# opto4.net
KiCad netlist of a schematic drawn in EAGLE
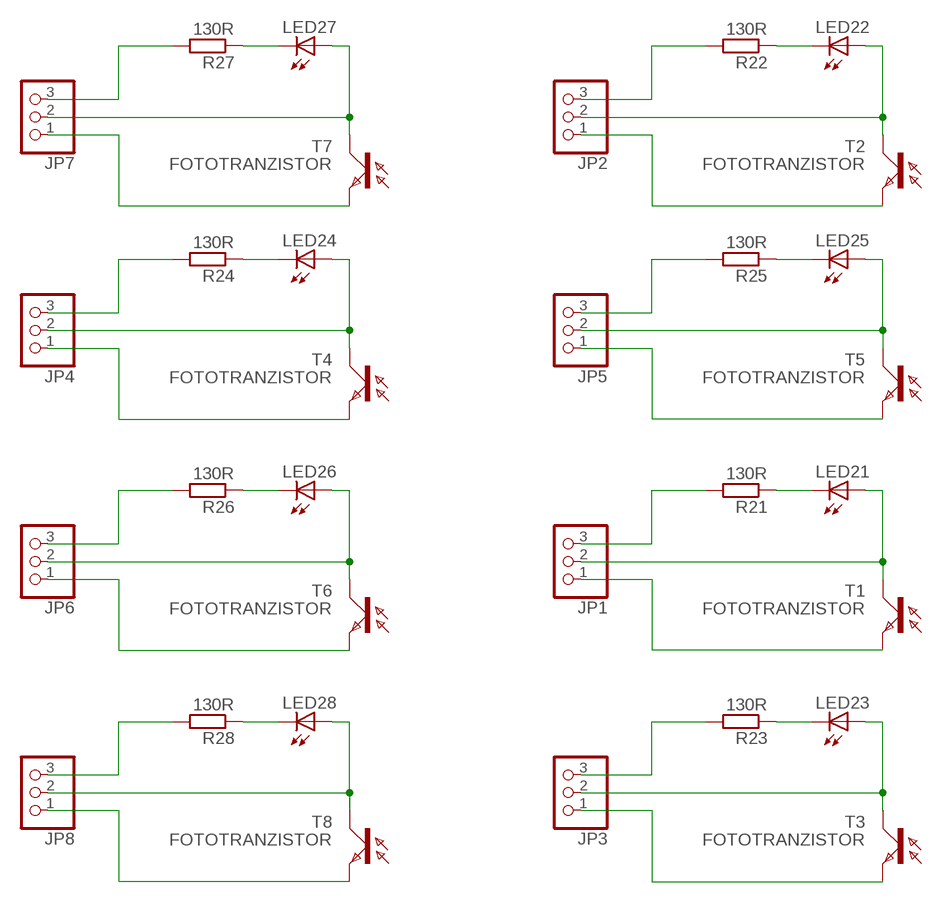
[diagram p0: schematic, sheet 1]

(export (version "E")
  (design (tool "Eeschema 10.0.6"))
  (components
    (comp (ref "JP1")
      (value "PINHD-1X3/90")
      (footprint "eagle-import:1X03_90")
      (libsource (lib "eagle-import") (part "PINHD-1X3/90"))
    )
    (comp (ref "JP2")
      (value "PINHD-1X3/90")
      (footprint "eagle-import:1X03_90")
      (libsource (lib "eagle-import") (part "PINHD-1X3/90"))
    )
    (comp (ref "JP3")
      (value "PINHD-1X3/90")
      (footprint "eagle-import:1X03_90")
      (libsource (lib "eagle-import") (part "PINHD-1X3/90"))
    )
    (comp (ref "JP4")
      (value "PINHD-1X3/90")
      (footprint "eagle-import:1X03_90")
      (libsource (lib "eagle-import") (part "PINHD-1X3/90"))
    )
    (comp (ref "JP5")
      (value "PINHD-1X3/90")
      (footprint "eagle-import:1X03_90")
      (libsource (lib "eagle-import") (part "PINHD-1X3/90"))
    )
    (comp (ref "JP6")
      (value "PINHD-1X3/90")
      (footprint "eagle-import:1X03_90")
      (libsource (lib "eagle-import") (part "PINHD-1X3/90"))
    )
    (comp (ref "JP7")
      (value "PINHD-1X3/90")
      (footprint "eagle-import:1X03_90")
      (libsource (lib "eagle-import") (part "PINHD-1X3/90"))
    )
    (comp (ref "JP8")
      (value "PINHD-1X3/90")
      (footprint "eagle-import:1X03_90")
      (libsource (lib "eagle-import") (part "PINHD-1X3/90"))
    )
    (comp (ref "LED21")
      (value "LED3MM")
      (footprint "eagle-import:LED3MM")
      (libsource (lib "eagle-import") (part "LED3MM"))
    )
    (comp (ref "LED22")
      (value "LED3MM")
      (footprint "eagle-import:LED3MM")
      (libsource (lib "eagle-import") (part "LED3MM"))
    )
    (comp (ref "LED23")
      (value "LED3MM")
      (footprint "eagle-import:LED3MM")
      (libsource (lib "eagle-import") (part "LED3MM"))
    )
    (comp (ref "LED24")
      (value "LED3MM")
      (footprint "eagle-import:LED3MM")
      (libsource (lib "eagle-import") (part "LED3MM"))
    )
    (comp (ref "LED25")
      (value "LED3MM")
      (footprint "eagle-import:LED3MM")
      (libsource (lib "eagle-import") (part "LED3MM"))
    )
    (comp (ref "LED26")
      (value "LED3MM")
      (footprint "eagle-import:LED3MM")
      (libsource (lib "eagle-import") (part "LED3MM"))
    )
    (comp (ref "LED27")
      (value "LED3MM")
      (footprint "eagle-import:LED3MM")
      (libsource (lib "eagle-import") (part "LED3MM"))
    )
    (comp (ref "LED28")
      (value "LED3MM")
      (footprint "eagle-import:LED3MM")
      (libsource (lib "eagle-import") (part "LED3MM"))
    )
    (comp (ref "R21")
      (value "130R")
      (footprint "eagle-import:R1206")
      (libsource (lib "eagle-import") (part "R-EU_R1206"))
    )
    (comp (ref "R22")
      (value "130R")
      (footprint "eagle-import:R1206")
      (libsource (lib "eagle-import") (part "R-EU_R1206"))
    )
    (comp (ref "R23")
      (value "130R")
      (footprint "eagle-import:R1206")
      (libsource (lib "eagle-import") (part "R-EU_R1206"))
    )
    (comp (ref "R24")
      (value "130R")
      (footprint "eagle-import:R1206")
      (libsource (lib "eagle-import") (part "R-EU_R1206"))
    )
    (comp (ref "R25")
      (value "130R")
      (footprint "eagle-import:R1206")
      (libsource (lib "eagle-import") (part "R-EU_R1206"))
    )
    (comp (ref "R26")
      (value "130R")
      (footprint "eagle-import:R1206")
      (libsource (lib "eagle-import") (part "R-EU_R1206"))
    )
    (comp (ref "R27")
      (value "130R")
      (footprint "eagle-import:R1206")
      (libsource (lib "eagle-import") (part "R-EU_R1206"))
    )
    (comp (ref "R28")
      (value "130R")
      (footprint "eagle-import:R1206")
      (libsource (lib "eagle-import") (part "R-EU_R1206"))
    )
    (comp (ref "T1")
      (value "FOTOTRANZISTOR")
      (footprint "eagle-import:BPX81")
      (libsource (lib "eagle-import") (part "FOTOTRANZISTOR"))
    )
    (comp (ref "T2")
      (value "FOTOTRANZISTOR")
      (footprint "eagle-import:BPX81")
      (libsource (lib "eagle-import") (part "FOTOTRANZISTOR"))
    )
    (comp (ref "T3")
      (value "FOTOTRANZISTOR")
      (footprint "eagle-import:BPX81")
      (libsource (lib "eagle-import") (part "FOTOTRANZISTOR"))
    )
    (comp (ref "T4")
      (value "FOTOTRANZISTOR")
      (footprint "eagle-import:BPX81")
      (libsource (lib "eagle-import") (part "FOTOTRANZISTOR"))
    )
    (comp (ref "T5")
      (value "FOTOTRANZISTOR")
      (footprint "eagle-import:BPX81")
      (libsource (lib "eagle-import") (part "FOTOTRANZISTOR"))
    )
    (comp (ref "T6")
      (value "FOTOTRANZISTOR")
      (footprint "eagle-import:BPX81")
      (libsource (lib "eagle-import") (part "FOTOTRANZISTOR"))
    )
    (comp (ref "T7")
      (value "FOTOTRANZISTOR")
      (footprint "eagle-import:BPX81")
      (libsource (lib "eagle-import") (part "FOTOTRANZISTOR"))
    )
    (comp (ref "T8")
      (value "FOTOTRANZISTOR")
      (footprint "eagle-import:BPX81")
      (libsource (lib "eagle-import") (part "FOTOTRANZISTOR"))
    )
  )
  (nets
    (net (code "1") (name "Net-(JP1-Pad1)") (class "Default")
      (node (ref "JP1") (pin "1") (pinfunction "1_1") (pintype "passive"))
      (node (ref "T1") (pin "E") (pinfunction "E_E") (pintype "passive"))
    )
    (net (code "2") (name "Net-(JP1-Pad2)") (class "Default")
      (node (ref "JP1") (pin "2") (pinfunction "2_2") (pintype "passive"))
      (node (ref "LED21") (pin "A") (pinfunction "A_A") (pintype "passive"))
      (node (ref "T1") (pin "C") (pinfunction "C_C") (pintype "passive"))
    )
    (net (code "3") (name "Net-(JP1-Pad3)") (class "Default")
      (node (ref "JP1") (pin "3") (pinfunction "3_3") (pintype "passive"))
      (node (ref "R21") (pin "2") (pinfunction "2_2") (pintype "passive"))
    )
    (net (code "4") (name "Net-(JP2-Pad1)") (class "Default")
      (node (ref "JP2") (pin "1") (pinfunction "1_1") (pintype "passive"))
      (node (ref "T2") (pin "E") (pinfunction "E_E") (pintype "passive"))
    )
    (net (code "5") (name "Net-(JP2-Pad2)") (class "Default")
      (node (ref "JP2") (pin "2") (pinfunction "2_2") (pintype "passive"))
      (node (ref "LED22") (pin "A") (pinfunction "A_A") (pintype "passive"))
      (node (ref "T2") (pin "C") (pinfunction "C_C") (pintype "passive"))
    )
    (net (code "6") (name "Net-(JP2-Pad3)") (class "Default")
      (node (ref "JP2") (pin "3") (pinfunction "3_3") (pintype "passive"))
      (node (ref "R22") (pin "2") (pinfunction "2_2") (pintype "passive"))
    )
    (net (code "7") (name "Net-(JP3-Pad1)") (class "Default")
      (node (ref "JP3") (pin "1") (pinfunction "1_1") (pintype "passive"))
      (node (ref "T3") (pin "E") (pinfunction "E_E") (pintype "passive"))
    )
    (net (code "8") (name "Net-(JP3-Pad2)") (class "Default")
      (node (ref "JP3") (pin "2") (pinfunction "2_2") (pintype "passive"))
      (node (ref "LED23") (pin "A") (pinfunction "A_A") (pintype "passive"))
      (node (ref "T3") (pin "C") (pinfunction "C_C") (pintype "passive"))
    )
    (net (code "9") (name "Net-(JP3-Pad3)") (class "Default")
      (node (ref "JP3") (pin "3") (pinfunction "3_3") (pintype "passive"))
      (node (ref "R23") (pin "2") (pinfunction "2_2") (pintype "passive"))
    )
    (net (code "10") (name "Net-(JP4-Pad1)") (class "Default")
      (node (ref "JP4") (pin "1") (pinfunction "1_1") (pintype "passive"))
      (node (ref "T4") (pin "E") (pinfunction "E_E") (pintype "passive"))
    )
    (net (code "11") (name "Net-(JP4-Pad2)") (class "Default")
      (node (ref "JP4") (pin "2") (pinfunction "2_2") (pintype "passive"))
      (node (ref "LED24") (pin "A") (pinfunction "A_A") (pintype "passive"))
      (node (ref "T4") (pin "C") (pinfunction "C_C") (pintype "passive"))
    )
    (net (code "12") (name "Net-(JP4-Pad3)") (class "Default")
      (node (ref "JP4") (pin "3") (pinfunction "3_3") (pintype "passive"))
      (node (ref "R24") (pin "2") (pinfunction "2_2") (pintype "passive"))
    )
    (net (code "13") (name "Net-(JP5-Pad1)") (class "Default")
      (node (ref "JP5") (pin "1") (pinfunction "1_1") (pintype "passive"))
      (node (ref "T5") (pin "E") (pinfunction "E_E") (pintype "passive"))
    )
    (net (code "14") (name "Net-(JP5-Pad2)") (class "Default")
      (node (ref "JP5") (pin "2") (pinfunction "2_2") (pintype "passive"))
      (node (ref "LED25") (pin "A") (pinfunction "A_A") (pintype "passive"))
      (node (ref "T5") (pin "C") (pinfunction "C_C") (pintype "passive"))
    )
    (net (code "15") (name "Net-(JP5-Pad3)") (class "Default")
      (node (ref "JP5") (pin "3") (pinfunction "3_3") (pintype "passive"))
      (node (ref "R25") (pin "2") (pinfunction "2_2") (pintype "passive"))
    )
    (net (code "16") (name "Net-(JP6-Pad1)") (class "Default")
      (node (ref "JP6") (pin "1") (pinfunction "1_1") (pintype "passive"))
      (node (ref "T6") (pin "E") (pinfunction "E_E") (pintype "passive"))
    )
    (net (code "17") (name "Net-(JP6-Pad2)") (class "Default")
      (node (ref "JP6") (pin "2") (pinfunction "2_2") (pintype "passive"))
      (node (ref "LED26") (pin "A") (pinfunction "A_A") (pintype "passive"))
      (node (ref "T6") (pin "C") (pinfunction "C_C") (pintype "passive"))
    )
    (net (code "18") (name "Net-(JP6-Pad3)") (class "Default")
      (node (ref "JP6") (pin "3") (pinfunction "3_3") (pintype "passive"))
      (node (ref "R26") (pin "2") (pinfunction "2_2") (pintype "passive"))
    )
    (net (code "19") (name "Net-(JP7-Pad1)") (class "Default")
      (node (ref "JP7") (pin "1") (pinfunction "1_1") (pintype "passive"))
      (node (ref "T7") (pin "E") (pinfunction "E_E") (pintype "passive"))
    )
    (net (code "20") (name "Net-(JP7-Pad2)") (class "Default")
      (node (ref "JP7") (pin "2") (pinfunction "2_2") (pintype "passive"))
      (node (ref "LED27") (pin "A") (pinfunction "A_A") (pintype "passive"))
      (node (ref "T7") (pin "C") (pinfunction "C_C") (pintype "passive"))
    )
    (net (code "21") (name "Net-(JP7-Pad3)") (class "Default")
      (node (ref "JP7") (pin "3") (pinfunction "3_3") (pintype "passive"))
      (node (ref "R27") (pin "2") (pinfunction "2_2") (pintype "passive"))
    )
    (net (code "22") (name "Net-(JP8-Pad1)") (class "Default")
      (node (ref "JP8") (pin "1") (pinfunction "1_1") (pintype "passive"))
      (node (ref "T8") (pin "E") (pinfunction "E_E") (pintype "passive"))
    )
    (net (code "23") (name "Net-(JP8-Pad2)") (class "Default")
      (node (ref "JP8") (pin "2") (pinfunction "2_2") (pintype "passive"))
      (node (ref "LED28") (pin "A") (pinfunction "A_A") (pintype "passive"))
      (node (ref "T8") (pin "C") (pinfunction "C_C") (pintype "passive"))
    )
    (net (code "24") (name "Net-(JP8-Pad3)") (class "Default")
      (node (ref "JP8") (pin "3") (pinfunction "3_3") (pintype "passive"))
      (node (ref "R28") (pin "2") (pinfunction "2_2") (pintype "passive"))
    )
    (net (code "25") (name "Net-(LED21-C)") (class "Default")
      (node (ref "LED21") (pin "K") (pinfunction "C_K") (pintype "passive"))
      (node (ref "R21") (pin "1") (pinfunction "1_1") (pintype "passive"))
    )
    (net (code "26") (name "Net-(LED22-C)") (class "Default")
      (node (ref "LED22") (pin "K") (pinfunction "C_K") (pintype "passive"))
      (node (ref "R22") (pin "1") (pinfunction "1_1") (pintype "passive"))
    )
    (net (code "27") (name "Net-(LED23-C)") (class "Default")
      (node (ref "LED23") (pin "K") (pinfunction "C_K") (pintype "passive"))
      (node (ref "R23") (pin "1") (pinfunction "1_1") (pintype "passive"))
    )
    (net (code "28") (name "Net-(LED24-C)") (class "Default")
      (node (ref "LED24") (pin "K") (pinfunction "C_K") (pintype "passive"))
      (node (ref "R24") (pin "1") (pinfunction "1_1") (pintype "passive"))
    )
    (net (code "29") (name "Net-(LED25-C)") (class "Default")
      (node (ref "LED25") (pin "K") (pinfunction "C_K") (pintype "passive"))
      (node (ref "R25") (pin "1") (pinfunction "1_1") (pintype "passive"))
    )
    (net (code "30") (name "Net-(LED26-C)") (class "Default")
      (node (ref "LED26") (pin "K") (pinfunction "C_K") (pintype "passive"))
      (node (ref "R26") (pin "1") (pinfunction "1_1") (pintype "passive"))
    )
    (net (code "31") (name "Net-(LED27-C)") (class "Default")
      (node (ref "LED27") (pin "K") (pinfunction "C_K") (pintype "passive"))
      (node (ref "R27") (pin "1") (pinfunction "1_1") (pintype "passive"))
    )
    (net (code "32") (name "Net-(LED28-C)") (class "Default")
      (node (ref "LED28") (pin "K") (pinfunction "C_K") (pintype "passive"))
      (node (ref "R28") (pin "1") (pinfunction "1_1") (pintype "passive"))
    )
  )
)
